# stroboskop.net
KiCad netlist of a schematic drawn in EAGLE
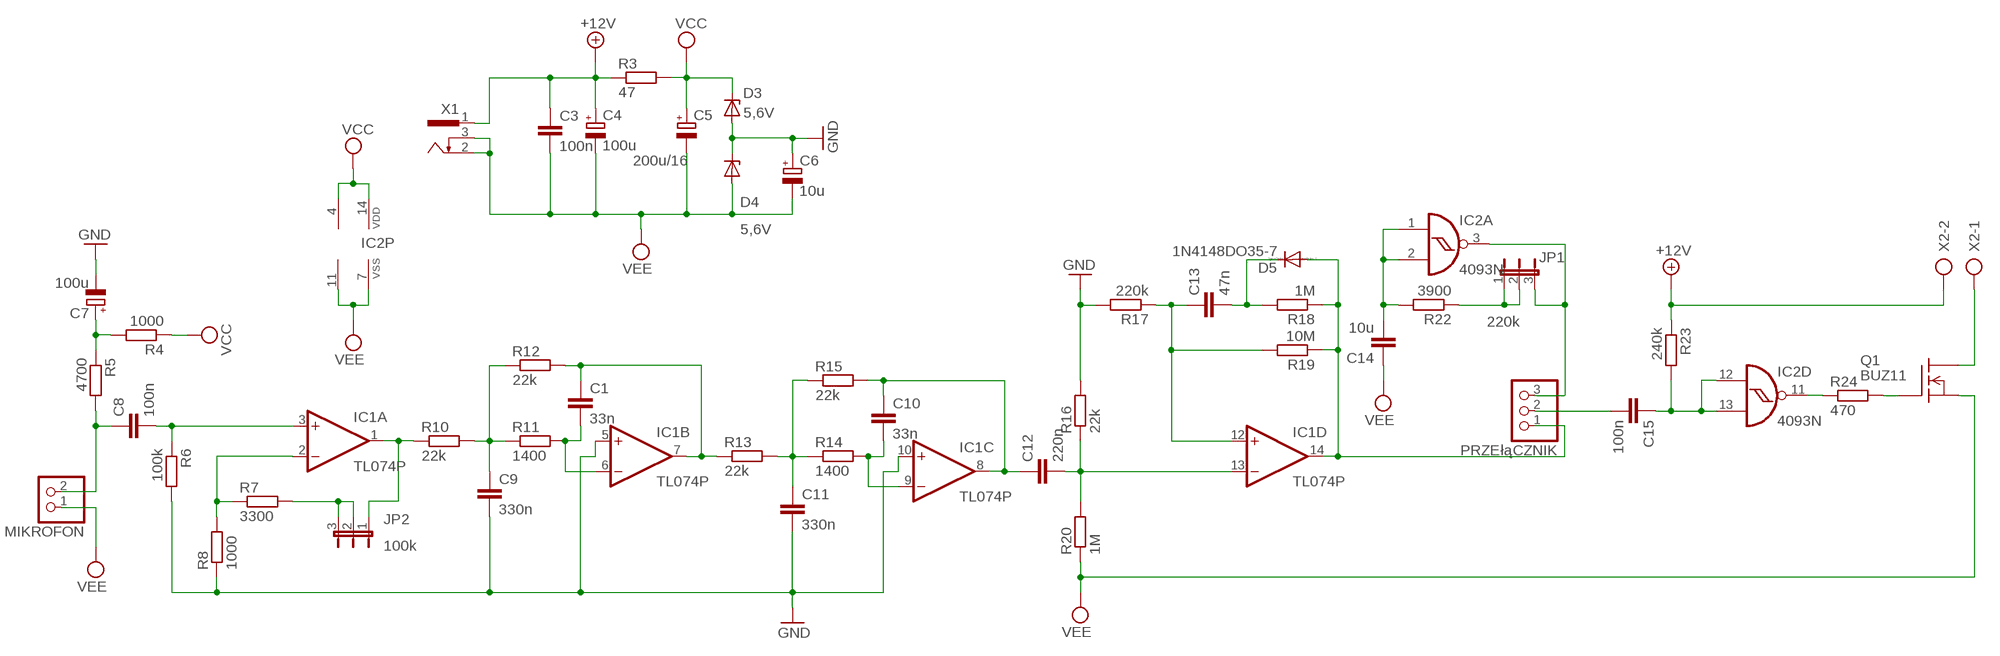
[diagram p0: schematic, sheet 1]

(export (version "E")
  (design (tool "Eeschema 10.0.6"))
  (components
    (comp (ref "C1")
      (value "33n")
      (footprint "eagle-import:C025-025X050")
      (libsource (lib "eagle-import") (part "C-EU025-025X050"))
    )
    (comp (ref "C3")
      (value "100n")
      (footprint "eagle-import:C025-025X050")
      (libsource (lib "eagle-import") (part "C-EU025-025X050"))
    )
    (comp (ref "C4")
      (value "100u")
      (footprint "eagle-import:E2,5-6E")
      (libsource (lib "eagle-import") (part "CPOL-EUE2,5-6E"))
    )
    (comp (ref "C5")
      (value "200u/16")
      (footprint "eagle-import:E2,5-6E")
      (libsource (lib "eagle-import") (part "CPOL-EUE2,5-6E"))
    )
    (comp (ref "C6")
      (value "10u")
      (footprint "eagle-import:E2,5-6E")
      (libsource (lib "eagle-import") (part "CPOL-EUE2,5-6E"))
    )
    (comp (ref "C7")
      (value "100u")
      (footprint "eagle-import:E2,5-6E")
      (libsource (lib "eagle-import") (part "CPOL-EUE2,5-6E"))
    )
    (comp (ref "C8")
      (value "100n")
      (footprint "eagle-import:C025-025X050")
      (libsource (lib "eagle-import") (part "C-EU025-025X050"))
    )
    (comp (ref "C9")
      (value "330n")
      (footprint "eagle-import:C025-025X050")
      (libsource (lib "eagle-import") (part "C-EU025-025X050"))
    )
    (comp (ref "C10")
      (value "33n")
      (footprint "eagle-import:C025-025X050")
      (libsource (lib "eagle-import") (part "C-EU025-025X050"))
    )
    (comp (ref "C11")
      (value "330n")
      (footprint "eagle-import:C025-025X050")
      (libsource (lib "eagle-import") (part "C-EU025-025X050"))
    )
    (comp (ref "C12")
      (value "220n")
      (footprint "eagle-import:C025-025X050")
      (libsource (lib "eagle-import") (part "C-EU025-025X050"))
    )
    (comp (ref "C13")
      (value "47n")
      (footprint "eagle-import:C025-025X050")
      (libsource (lib "eagle-import") (part "C-EU025-025X050"))
    )
    (comp (ref "C14")
      (value "10u")
      (footprint "eagle-import:C025-025X050")
      (libsource (lib "eagle-import") (part "C-EU025-025X050"))
    )
    (comp (ref "C15")
      (value "100n")
      (footprint "eagle-import:C025-025X050")
      (libsource (lib "eagle-import") (part "C-EU025-025X050"))
    )
    (comp (ref "D3")
      (value "5,6V")
      (footprint "eagle-import:DO35Z10")
      (libsource (lib "eagle-import") (part "1N821"))
    )
    (comp (ref "D4")
      (value "5,6V")
      (footprint "eagle-import:DO35Z10")
      (libsource (lib "eagle-import") (part "1N821"))
    )
    (comp (ref "D5")
      (value "1N4148DO35-7")
      (footprint "eagle-import:DO35-7")
      (libsource (lib "eagle-import") (part "1N4148DO35-7"))
    )
    (comp (ref "IC1")
      (value "TL074P")
      (footprint "eagle-import:DIL14")
      (libsource (lib "eagle-import") (part "TL074P"))
    )
    (comp (ref "IC2")
      (value "4093N")
      (footprint "eagle-import:DIL14")
      (libsource (lib "eagle-import") (part "4093N"))
    )
    (comp (ref "JP1")
      (value "220k")
      (footprint "eagle-import:JP2")
      (libsource (lib "eagle-import") (part "JP2E"))
    )
    (comp (ref "JP2")
      (value "100k")
      (footprint "eagle-import:JP2")
      (libsource (lib "eagle-import") (part "JP2E"))
    )
    (comp (ref "MIKROFON")
      (value "PINHD-1X2")
      (footprint "eagle-import:1X02")
      (libsource (lib "eagle-import") (part "PINHD-1X2"))
    )
    (comp (ref "PRZEłąCZNIK")
      (value "PINHD-1X3")
      (footprint "eagle-import:1X03")
      (libsource (lib "eagle-import") (part "PINHD-1X3"))
    )
    (comp (ref "Q1")
      (value "BUZ11")
      (footprint "eagle-import:TO220")
      (libsource (lib "eagle-import") (part "BUZ11"))
    )
    (comp (ref "R3")
      (value "47")
      (footprint "eagle-import:0204_5")
      (libsource (lib "eagle-import") (part "R-EU_0204/5"))
    )
    (comp (ref "R4")
      (value "1000")
      (footprint "eagle-import:0204_5")
      (libsource (lib "eagle-import") (part "R-EU_0204/5"))
    )
    (comp (ref "R5")
      (value "4700")
      (footprint "eagle-import:0204_5")
      (libsource (lib "eagle-import") (part "R-EU_0204/5"))
    )
    (comp (ref "R6")
      (value "100k")
      (footprint "eagle-import:0204_5")
      (libsource (lib "eagle-import") (part "R-EU_0204/5"))
    )
    (comp (ref "R7")
      (value "3300")
      (footprint "eagle-import:0204_5")
      (libsource (lib "eagle-import") (part "R-EU_0204/5"))
    )
    (comp (ref "R8")
      (value "1000")
      (footprint "eagle-import:0204_5")
      (libsource (lib "eagle-import") (part "R-EU_0204/5"))
    )
    (comp (ref "R10")
      (value "22k")
      (footprint "eagle-import:0204_5")
      (libsource (lib "eagle-import") (part "R-EU_0204/5"))
    )
    (comp (ref "R11")
      (value "1400")
      (footprint "eagle-import:0204_5")
      (libsource (lib "eagle-import") (part "R-EU_0204/5"))
    )
    (comp (ref "R12")
      (value "22k")
      (footprint "eagle-import:0204_5")
      (libsource (lib "eagle-import") (part "R-EU_0204/5"))
    )
    (comp (ref "R13")
      (value "22k")
      (footprint "eagle-import:0204_5")
      (libsource (lib "eagle-import") (part "R-EU_0204/5"))
    )
    (comp (ref "R14")
      (value "1400")
      (footprint "eagle-import:0204_5")
      (libsource (lib "eagle-import") (part "R-EU_0204/5"))
    )
    (comp (ref "R15")
      (value "22k")
      (footprint "eagle-import:0204_5")
      (libsource (lib "eagle-import") (part "R-EU_0204/5"))
    )
    (comp (ref "R16")
      (value "22k")
      (footprint "eagle-import:0204_5")
      (libsource (lib "eagle-import") (part "R-EU_0204/5"))
    )
    (comp (ref "R17")
      (value "220k")
      (footprint "eagle-import:0204_5")
      (libsource (lib "eagle-import") (part "R-EU_0204/5"))
    )
    (comp (ref "R18")
      (value "1M")
      (footprint "eagle-import:0204_5")
      (libsource (lib "eagle-import") (part "R-EU_0204/5"))
    )
    (comp (ref "R19")
      (value "10M")
      (footprint "eagle-import:0204_5")
      (libsource (lib "eagle-import") (part "R-EU_0204/5"))
    )
    (comp (ref "R20")
      (value "1M")
      (footprint "eagle-import:0204_5")
      (libsource (lib "eagle-import") (part "R-EU_0204/5"))
    )
    (comp (ref "R22")
      (value "3900")
      (footprint "eagle-import:0204_5")
      (libsource (lib "eagle-import") (part "R-EU_0204/5"))
    )
    (comp (ref "R23")
      (value "240k")
      (footprint "eagle-import:0204_5")
      (libsource (lib "eagle-import") (part "R-EU_0204/5"))
    )
    (comp (ref "R24")
      (value "470")
      (footprint "eagle-import:0204_5")
      (libsource (lib "eagle-import") (part "R-EU_0204/5"))
    )
    (comp (ref "X1")
      (value "733980-62")
      (footprint "eagle-import:733980-62")
      (libsource (lib "eagle-import") (part "73398?0-62"))
    )
    (comp (ref "X2")
      (value "AK300/2")
      (footprint "eagle-import:AK300_2")
      (libsource (lib "eagle-import") (part "AK300/2"))
    )
  )
  (nets
    (net (code "1") (name "+12V") (class "Default")
      (node (ref "C3") (pin "1") (pinfunction "1_1") (pintype "passive"))
      (node (ref "C4") (pin "+") (pinfunction "+_+") (pintype "passive"))
      (node (ref "R23") (pin "1") (pinfunction "1_1") (pintype "passive"))
      (node (ref "R3") (pin "1") (pinfunction "1_1") (pintype "passive"))
      (node (ref "X1") (pin "1") (pinfunction "1_1") (pintype "passive"))
      (node (ref "X2") (pin "2") (pinfunction "KL_2") (pintype "passive"))
    )
    (net (code "2") (name "GND") (class "Default")
      (node (ref "C11") (pin "2") (pinfunction "2_2") (pintype "passive"))
      (node (ref "C6") (pin "+") (pinfunction "+_+") (pintype "passive"))
      (node (ref "C7") (pin "-") (pinfunction "-_-") (pintype "passive"))
      (node (ref "C9") (pin "2") (pinfunction "2_2") (pintype "passive"))
      (node (ref "D3") (pin "A") (pinfunction "A_A") (pintype "passive"))
      (node (ref "D4") (pin "C") (pinfunction "C_C") (pintype "passive"))
      (node (ref "IC1") (pin "10") (pinfunction "+IN_10") (pintype "input"))
      (node (ref "IC1") (pin "5") (pinfunction "+IN_5") (pintype "input"))
      (node (ref "R16") (pin "2") (pinfunction "2_2") (pintype "passive"))
      (node (ref "R17") (pin "2") (pinfunction "2_2") (pintype "passive"))
      (node (ref "R6") (pin "2") (pinfunction "2_2") (pintype "passive"))
      (node (ref "R8") (pin "1") (pinfunction "1_1") (pintype "passive"))
    )
    (net (code "3") (name "Net-(C7-Pad+)") (class "Default")
      (node (ref "C7") (pin "+") (pinfunction "+_+") (pintype "passive"))
      (node (ref "R4") (pin "2") (pinfunction "2_2") (pintype "passive"))
      (node (ref "R5") (pin "1") (pinfunction "1_1") (pintype "passive"))
    )
    (net (code "4") (name "Net-(C8-Pad1)") (class "Default")
      (node (ref "C8") (pin "1") (pinfunction "1_1") (pintype "passive"))
      (node (ref "MIKROFON") (pin "2") (pinfunction "2_2") (pintype "passive"))
      (node (ref "R5") (pin "2") (pinfunction "2_2") (pintype "passive"))
    )
    (net (code "5") (name "Net-(C9-Pad1)") (class "Default")
      (node (ref "C9") (pin "1") (pinfunction "1_1") (pintype "passive"))
      (node (ref "R10") (pin "2") (pinfunction "2_2") (pintype "passive"))
      (node (ref "R11") (pin "1") (pinfunction "1_1") (pintype "passive"))
      (node (ref "R12") (pin "1") (pinfunction "1_1") (pintype "passive"))
    )
    (net (code "6") (name "Net-(C11-Pad1)") (class "Default")
      (node (ref "C11") (pin "1") (pinfunction "1_1") (pintype "passive"))
      (node (ref "R13") (pin "2") (pinfunction "2_2") (pintype "passive"))
      (node (ref "R14") (pin "1") (pinfunction "1_1") (pintype "passive"))
      (node (ref "R15") (pin "1") (pinfunction "1_1") (pintype "passive"))
    )
    (net (code "7") (name "Net-(C13-Pad2)") (class "Default")
      (node (ref "C13") (pin "2") (pinfunction "2_2") (pintype "passive"))
      (node (ref "D5") (pin "C") (pinfunction "C_C") (pintype "passive"))
      (node (ref "R18") (pin "2") (pinfunction "2_2") (pintype "passive"))
    )
    (net (code "8") (name "Net-(C15-Pad2)") (class "Default")
      (node (ref "C15") (pin "2") (pinfunction "2_2") (pintype "passive"))
      (node (ref "PRZEłąCZNIK") (pin "2") (pinfunction "2_2") (pintype "passive"))
    )
    (net (code "9") (name "Net-(IC1A-+IN)") (class "Default")
      (node (ref "C8") (pin "2") (pinfunction "2_2") (pintype "passive"))
      (node (ref "IC1") (pin "3") (pinfunction "+IN_3") (pintype "input"))
      (node (ref "R6") (pin "1") (pinfunction "1_1") (pintype "passive"))
    )
    (net (code "10") (name "Net-(IC1A--IN)") (class "Default")
      (node (ref "IC1") (pin "2") (pinfunction "-IN_2") (pintype "input"))
      (node (ref "R7") (pin "1") (pinfunction "1_1") (pintype "passive"))
      (node (ref "R8") (pin "2") (pinfunction "2_2") (pintype "passive"))
    )
    (net (code "11") (name "Net-(IC1A-OUT)") (class "Default")
      (node (ref "IC1") (pin "1") (pinfunction "OUT_1") (pintype "output"))
      (node (ref "JP2") (pin "1") (pinfunction "1_1") (pintype "passive"))
      (node (ref "R10") (pin "1") (pinfunction "1_1") (pintype "passive"))
    )
    (net (code "12") (name "Net-(IC1B--IN)") (class "Default")
      (node (ref "C1") (pin "2") (pinfunction "2_2") (pintype "passive"))
      (node (ref "IC1") (pin "6") (pinfunction "-IN_6") (pintype "input"))
      (node (ref "R11") (pin "2") (pinfunction "2_2") (pintype "passive"))
    )
    (net (code "13") (name "Net-(IC1B-OUT)") (class "Default")
      (node (ref "C1") (pin "1") (pinfunction "1_1") (pintype "passive"))
      (node (ref "IC1") (pin "7") (pinfunction "OUT_7") (pintype "output"))
      (node (ref "R12") (pin "2") (pinfunction "2_2") (pintype "passive"))
      (node (ref "R13") (pin "1") (pinfunction "1_1") (pintype "passive"))
    )
    (net (code "14") (name "Net-(IC1C--IN)") (class "Default")
      (node (ref "C10") (pin "2") (pinfunction "2_2") (pintype "passive"))
      (node (ref "IC1") (pin "9") (pinfunction "-IN_9") (pintype "input"))
      (node (ref "R14") (pin "2") (pinfunction "2_2") (pintype "passive"))
    )
    (net (code "15") (name "Net-(IC1C-OUT)") (class "Default")
      (node (ref "C10") (pin "1") (pinfunction "1_1") (pintype "passive"))
      (node (ref "C12") (pin "1") (pinfunction "1_1") (pintype "passive"))
      (node (ref "IC1") (pin "8") (pinfunction "OUT_8") (pintype "output"))
      (node (ref "R15") (pin "2") (pinfunction "2_2") (pintype "passive"))
    )
    (net (code "16") (name "Net-(IC1D-+IN)") (class "Default")
      (node (ref "C13") (pin "1") (pinfunction "1_1") (pintype "passive"))
      (node (ref "IC1") (pin "12") (pinfunction "+IN_12") (pintype "input"))
      (node (ref "R17") (pin "1") (pinfunction "1_1") (pintype "passive"))
      (node (ref "R19") (pin "2") (pinfunction "2_2") (pintype "passive"))
    )
    (net (code "17") (name "Net-(IC1D--IN)") (class "Default")
      (node (ref "C12") (pin "2") (pinfunction "2_2") (pintype "passive"))
      (node (ref "IC1") (pin "13") (pinfunction "-IN_13") (pintype "input"))
      (node (ref "R16") (pin "1") (pinfunction "1_1") (pintype "passive"))
      (node (ref "R20") (pin "2") (pinfunction "2_2") (pintype "passive"))
    )
    (net (code "18") (name "Net-(IC1D-OUT)") (class "Default")
      (node (ref "D5") (pin "A") (pinfunction "A_A") (pintype "passive"))
      (node (ref "IC1") (pin "14") (pinfunction "OUT_14") (pintype "output"))
      (node (ref "PRZEłąCZNIK") (pin "1") (pinfunction "1_1") (pintype "passive"))
      (node (ref "R18") (pin "1") (pinfunction "1_1") (pintype "passive"))
      (node (ref "R19") (pin "1") (pinfunction "1_1") (pintype "passive"))
    )
    (net (code "19") (name "Net-(IC2A-I0)") (class "Default")
      (node (ref "C14") (pin "2") (pinfunction "2_2") (pintype "passive"))
      (node (ref "IC2") (pin "1") (pinfunction "I0_1") (pintype "input"))
      (node (ref "IC2") (pin "2") (pinfunction "I1_2") (pintype "input"))
      (node (ref "R22") (pin "2") (pinfunction "2_2") (pintype "passive"))
    )
    (net (code "20") (name "Net-(IC2A-O)") (class "Default")
      (node (ref "IC2") (pin "3") (pinfunction "O_3") (pintype "output"))
      (node (ref "JP1") (pin "3") (pinfunction "3_3") (pintype "passive"))
      (node (ref "PRZEłąCZNIK") (pin "3") (pinfunction "3_3") (pintype "passive"))
    )
    (net (code "21") (name "Net-(IC2D-I0)") (class "Default")
      (node (ref "C15") (pin "1") (pinfunction "1_1") (pintype "passive"))
      (node (ref "IC2") (pin "12") (pinfunction "I0_12") (pintype "input"))
      (node (ref "IC2") (pin "13") (pinfunction "I1_13") (pintype "input"))
      (node (ref "R23") (pin "2") (pinfunction "2_2") (pintype "passive"))
    )
    (net (code "22") (name "Net-(IC2D-O)") (class "Default")
      (node (ref "IC2") (pin "11") (pinfunction "O_11") (pintype "output"))
      (node (ref "R24") (pin "1") (pinfunction "1_1") (pintype "passive"))
    )
    (net (code "23") (name "Net-(JP1-Pad1)") (class "Default")
      (node (ref "JP1") (pin "1") (pinfunction "1_1") (pintype "passive"))
      (node (ref "JP1") (pin "2") (pinfunction "2_2") (pintype "passive"))
      (node (ref "R22") (pin "1") (pinfunction "1_1") (pintype "passive"))
    )
    (net (code "24") (name "Net-(JP2-Pad2)") (class "Default")
      (node (ref "JP2") (pin "2") (pinfunction "2_2") (pintype "passive"))
      (node (ref "JP2") (pin "3") (pinfunction "3_3") (pintype "passive"))
      (node (ref "R7") (pin "2") (pinfunction "2_2") (pintype "passive"))
    )
    (net (code "25") (name "Net-(Q1-D)") (class "Default")
      (node (ref "Q1") (pin "2") (pinfunction "D_2") (pintype "passive"))
      (node (ref "X2") (pin "1") (pinfunction "KL_1") (pintype "passive"))
    )
    (net (code "26") (name "Net-(Q1-G)") (class "Default")
      (node (ref "Q1") (pin "1") (pinfunction "G_1") (pintype "passive"))
      (node (ref "R24") (pin "2") (pinfunction "2_2") (pintype "passive"))
    )
    (net (code "27") (name "VCC") (class "Default")
      (node (ref "C5") (pin "+") (pinfunction "+_+") (pintype "passive"))
      (node (ref "D3") (pin "C") (pinfunction "C_C") (pintype "passive"))
      (node (ref "IC1") (pin "4") (pinfunction "V+_4") (pintype "power_in"))
      (node (ref "IC2") (pin "14") (pinfunction "VDD_14") (pintype "power_in"))
      (node (ref "R3") (pin "2") (pinfunction "2_2") (pintype "passive"))
      (node (ref "R4") (pin "1") (pinfunction "1_1") (pintype "passive"))
    )
    (net (code "28") (name "VEE") (class "Default")
      (node (ref "C14") (pin "1") (pinfunction "1_1") (pintype "passive"))
      (node (ref "C3") (pin "2") (pinfunction "2_2") (pintype "passive"))
      (node (ref "C4") (pin "-") (pinfunction "-_-") (pintype "passive"))
      (node (ref "C5") (pin "-") (pinfunction "-_-") (pintype "passive"))
      (node (ref "C6") (pin "-") (pinfunction "-_-") (pintype "passive"))
      (node (ref "D4") (pin "A") (pinfunction "A_A") (pintype "passive"))
      (node (ref "IC1") (pin "11") (pinfunction "V-_11") (pintype "power_in"))
      (node (ref "IC2") (pin "7") (pinfunction "VSS_7") (pintype "power_in"))
      (node (ref "MIKROFON") (pin "1") (pinfunction "1_1") (pintype "passive"))
      (node (ref "Q1") (pin "3") (pinfunction "S_3") (pintype "passive"))
      (node (ref "R20") (pin "1") (pinfunction "1_1") (pintype "passive"))
      (node (ref "X1") (pin "2") (pinfunction "2_2") (pintype "passive"))
      (node (ref "X1") (pin "3") (pinfunction "3_3") (pintype "passive"))
    )
  )
)
